# 16_LMS2_RF2_Misc.net
KiCad netlist of a schematic drawn in Altium Designer
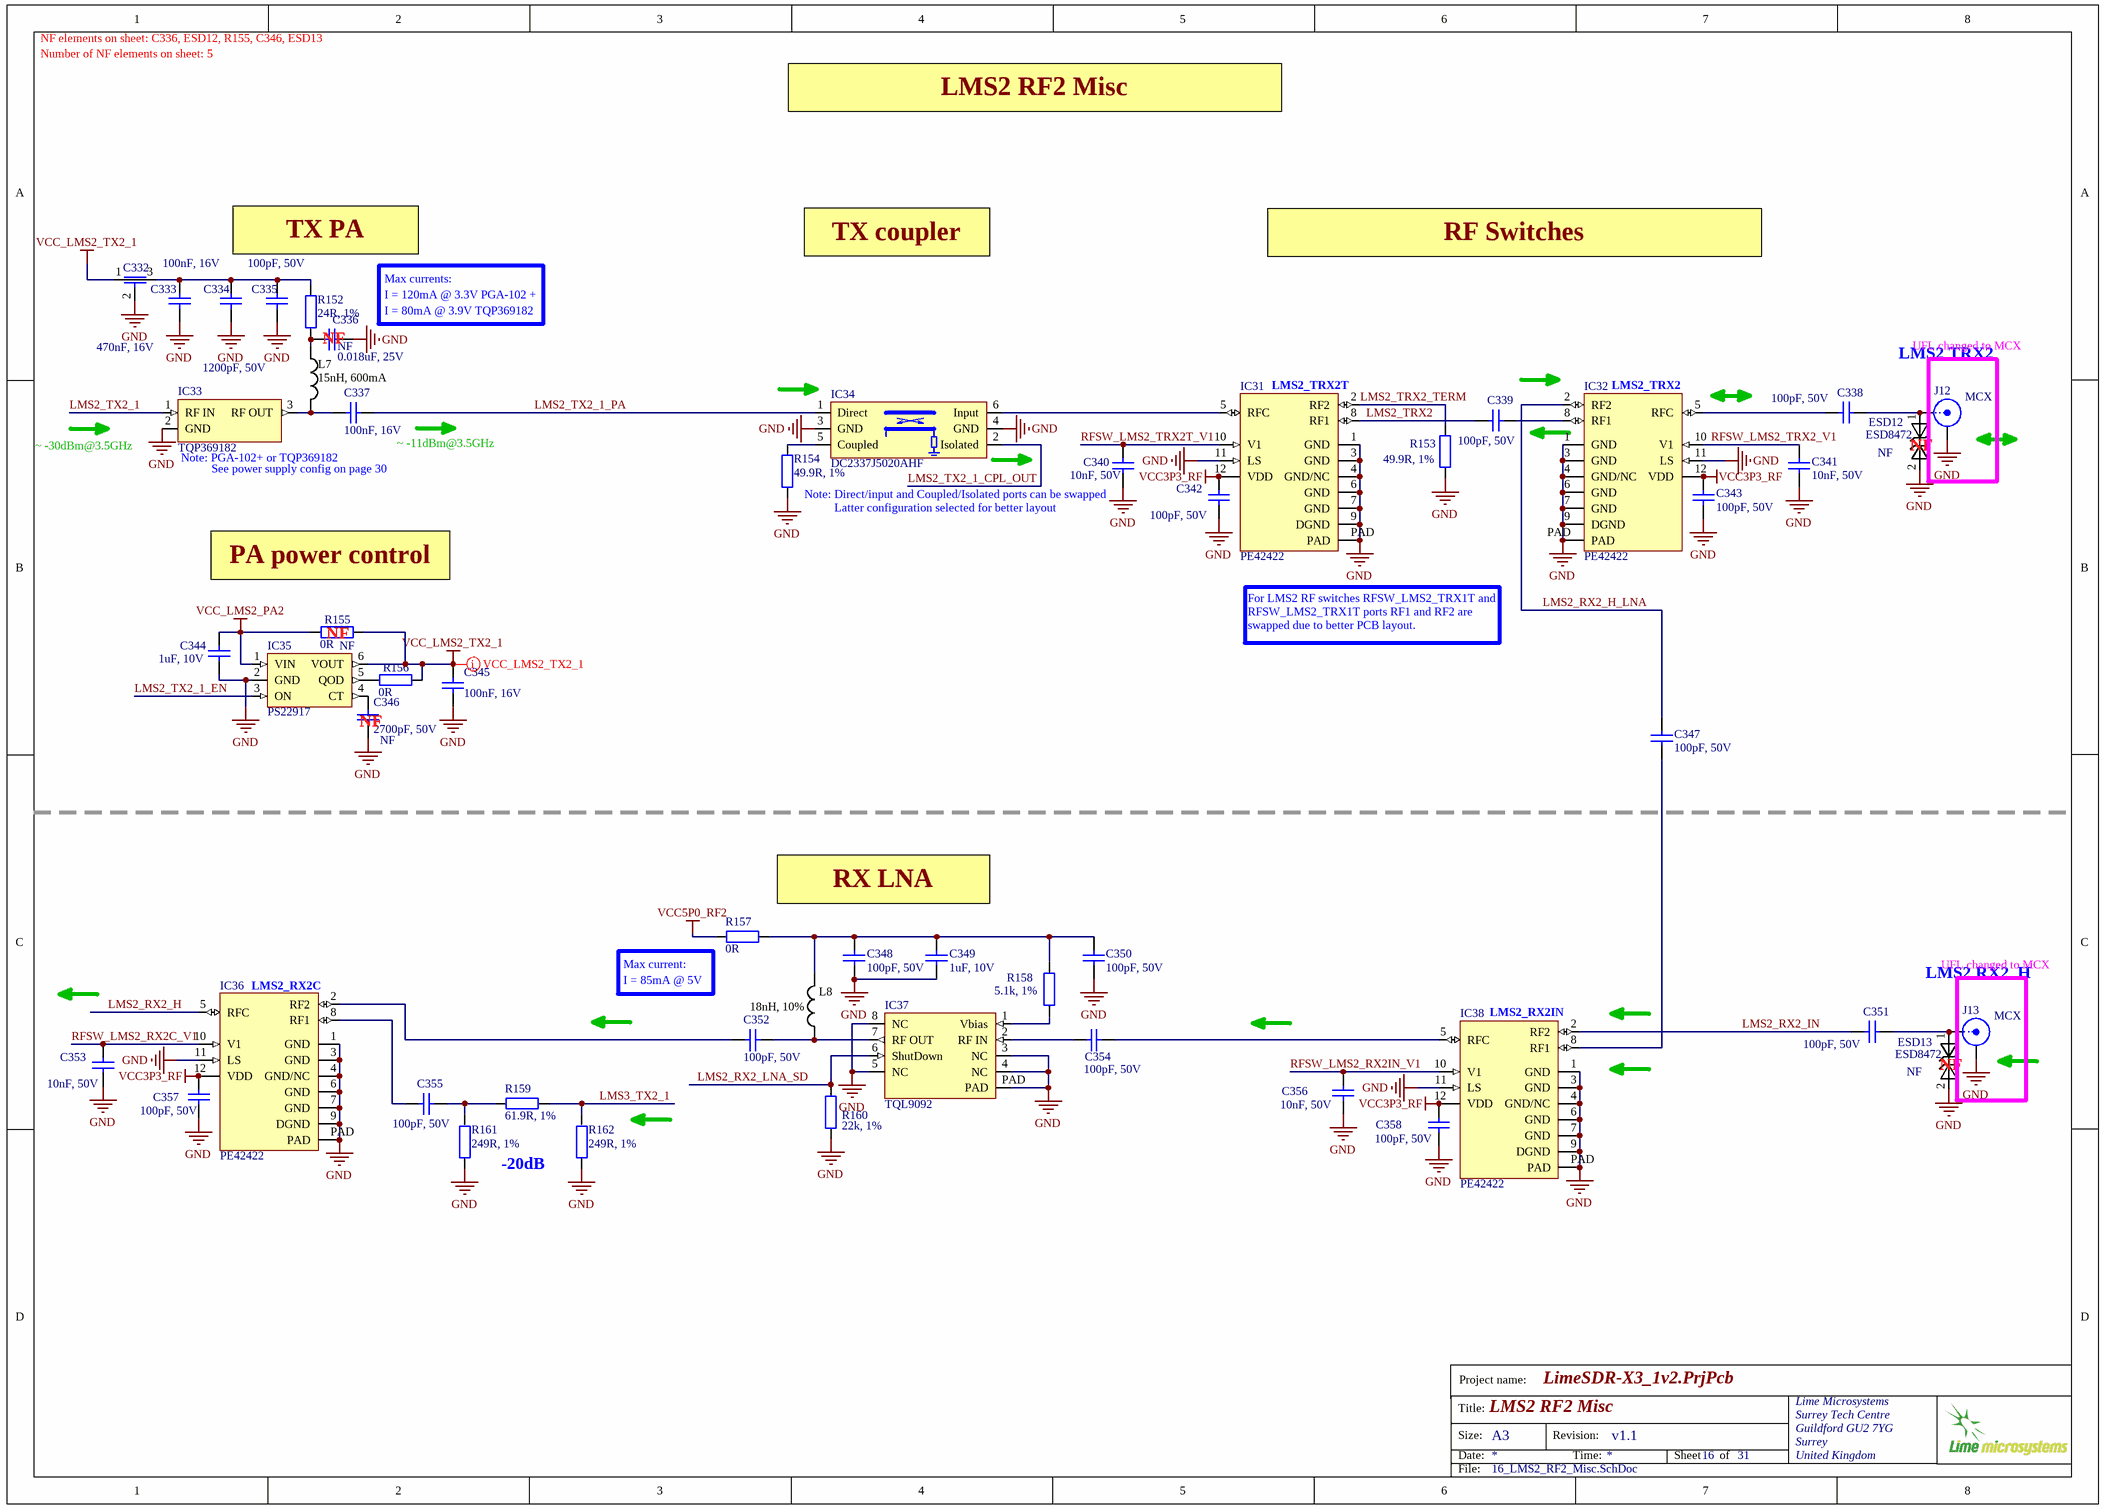
[diagram p0: 16_LMS2_RF2_Misc.SchDoc]

(export (version "E")
  (design (tool "Eeschema 10.0.6"))
  (components
    (comp (ref "C332")
      (value "470nF, 16V")
      (footprint "CAP0805_FEEDTHROUGH")
      (fields
        (field (name "MANUFACTURER") "Murata")
        (field (name "TOLERANCE") "20%")
        (field (name "VOLTAGE") "16V")
      )
      (libsource (lib "LimeMicroAltiumLib_schLib_r01") (part "Cap_feed_through"))
    )
    (comp (ref "C333")
      (value "100nF, 16V")
      (footprint "CAP0402")
      (fields (field (name "MANUFACTURER") "Murata Electronics") (field (name "TOLERANCE") "10 %"))
      (libsource (lib "") (part "Cap_0402_9"))
    )
    (comp (ref "C334")
      (value "1200pF, 50V")
      (footprint "CAP0402")
      (fields (field (name "MANUFACTURER") "Kemet") (field (name "TOLERANCE") "±5%"))
      (libsource (lib "LimeMicroAltiumLib_schLib") (part "Cap_0402"))
    )
    (comp (ref "C335")
      (value "100pF, 50V")
      (footprint "CAP0402")
      (fields (field (name "TOLERANCE") "±5%") (field (name "MANUFACTURER") "Yageo"))
      (libsource (lib "") (part "Cap_0402_9"))
    )
    (comp (ref "C336")
      (value "0.018uF, 25V")
      (footprint "CAP0402")
      (fields
        (field (name "ASSEMBLY INFO") "NF")
        (field (name "MANUFACTURER") "Yageo")
        (field (name "TOLERANCE") "10%")
      )
      (libsource (lib "LimeMicroAltiumLib_schLib") (part "Cap_0402"))
    )
    (comp (ref "C337")
      (value "100nF, 16V")
      (footprint "CAP0402")
      (fields (field (name "MANUFACTURER") "Murata Electronics") (field (name "TOLERANCE") "10 %"))
      (libsource (lib "LimeMicroAltiumLib_schLib") (part "Cap_0402"))
    )
    (comp (ref "C338")
      (value "100pF, 50V")
      (footprint "CAP0402")
      (fields (field (name "TOLERANCE") "±5%") (field (name "MANUFACTURER") "Yageo"))
      (libsource (lib "") (part "Cap_0402_1"))
    )
    (comp (ref "C339")
      (value "100pF, 50V")
      (footprint "CAP0402")
      (fields (field (name "TOLERANCE") "±5%") (field (name "MANUFACTURER") "Yageo"))
      (libsource (lib "") (part "Cap_0402_1"))
    )
    (comp (ref "C340")
      (value "10nF, 50V")
      (footprint "CAP0402")
      (fields
        (field (name "MANUFACTURER") "Murata Electronics North America")
        (field (name "TOLERANCE") "±10%")
      )
      (libsource (lib "") (part "Cap_0402_2"))
    )
    (comp (ref "C341")
      (value "10nF, 50V")
      (footprint "CAP0402")
      (fields
        (field (name "MANUFACTURER") "Murata Electronics North America")
        (field (name "TOLERANCE") "±10%")
      )
      (libsource (lib "") (part "Cap_0402_2"))
    )
    (comp (ref "C342")
      (value "100pF, 50V")
      (footprint "CAP0402")
      (fields (field (name "TOLERANCE") "±5%") (field (name "MANUFACTURER") "Yageo"))
      (libsource (lib "") (part "Cap_0402_6"))
    )
    (comp (ref "C343")
      (value "100pF, 50V")
      (footprint "CAP0402")
      (fields (field (name "TOLERANCE") "±5%") (field (name "MANUFACTURER") "Yageo"))
      (libsource (lib "") (part "Cap_0402_6"))
    )
    (comp (ref "C344")
      (value "1uF, 10V")
      (footprint "CAP0402")
      (fields (field (name "MANUFACTURER") "TDK"))
      (libsource (lib "") (part "Cap_0402_5"))
    )
    (comp (ref "C345")
      (value "100nF, 16V")
      (footprint "CAP0402")
      (fields (field (name "MANUFACTURER") "Murata Electronics") (field (name "TOLERANCE") "10 %"))
      (libsource (lib "") (part "Cap_0402_5"))
    )
    (comp (ref "C346")
      (value "2700pF, 50V")
      (footprint "CAP0402")
      (fields
        (field (name "ASSEMBLY INFO") "NF")
        (field (name "TOLERANCE") "±10%")
        (field (name "MANUFACTURER") "Murata Electronics North America")
      )
      (libsource (lib "") (part "Cap_0402_9"))
    )
    (comp (ref "C347")
      (value "100pF, 50V")
      (footprint "CAP0402")
      (fields (field (name "TOLERANCE") "±5%") (field (name "MANUFACTURER") "Yageo"))
      (libsource (lib "") (part "Cap_0402_1"))
    )
    (comp (ref "C348")
      (value "100pF, 50V")
      (footprint "CAP0402")
      (fields (field (name "TOLERANCE") "±5%") (field (name "MANUFACTURER") "Yageo"))
      (libsource (lib "") (part "Cap_0402_3"))
    )
    (comp (ref "C349")
      (value "1uF, 10V")
      (footprint "CAP0402")
      (fields (field (name "MANUFACTURER") "TDK"))
      (libsource (lib "") (part "Cap_0402_8"))
    )
    (comp (ref "C350")
      (value "100pF, 50V")
      (footprint "CAP0402")
      (fields (field (name "TOLERANCE") "±5%") (field (name "MANUFACTURER") "Yageo"))
      (libsource (lib "") (part "Cap_0402_3"))
    )
    (comp (ref "C351")
      (value "100pF, 50V")
      (footprint "CAP0402")
      (fields (field (name "TOLERANCE") "±5%") (field (name "MANUFACTURER") "Yageo"))
      (libsource (lib "") (part "Cap_0402_1"))
    )
    (comp (ref "C352")
      (value "100pF, 50V")
      (footprint "CAP0402")
      (fields (field (name "TOLERANCE") "±5%") (field (name "MANUFACTURER") "Yageo"))
      (libsource (lib "") (part "Cap_0402_5"))
    )
    (comp (ref "C353")
      (value "10nF, 50V")
      (footprint "CAP0402")
      (fields
        (field (name "MANUFACTURER") "Murata Electronics North America")
        (field (name "TOLERANCE") "±10%")
      )
      (libsource (lib "") (part "Cap_0402_4"))
    )
    (comp (ref "C354")
      (value "100pF, 50V")
      (footprint "CAP0402")
      (fields (field (name "TOLERANCE") "±5%") (field (name "MANUFACTURER") "Yageo"))
      (libsource (lib "") (part "Cap_0402_10"))
    )
    (comp (ref "C355")
      (value "100pF, 50V")
      (footprint "CAP0402")
      (fields (field (name "TOLERANCE") "±5%") (field (name "MANUFACTURER") "Yageo"))
      (libsource (lib "") (part "Cap_0402_1"))
    )
    (comp (ref "C356")
      (value "10nF, 50V")
      (footprint "CAP0402")
      (fields
        (field (name "MANUFACTURER") "Murata Electronics North America")
        (field (name "TOLERANCE") "±10%")
      )
      (libsource (lib "LimeMicroAltiumLib_schLib") (part "Cap_0402"))
    )
    (comp (ref "C357")
      (value "100pF, 50V")
      (footprint "CAP0402")
      (fields (field (name "TOLERANCE") "±5%") (field (name "MANUFACTURER") "Yageo"))
      (libsource (lib "") (part "Cap_0402_7"))
    )
    (comp (ref "C358")
      (value "100pF, 50V")
      (footprint "CAP0402")
      (fields (field (name "TOLERANCE") "±5%") (field (name "MANUFACTURER") "Yageo"))
      (libsource (lib "LimeMicroAltiumLib_schLib") (part "Cap_0402"))
    )
    (comp (ref "ESD12")
      (value "ESD8472")
      (footprint "ESD8472_X3DFN2")
      (fields (field (name "MANUFACTURER") "ON Semiconductor") (field (name "ASSEMBLY INFO") "NF"))
      (libsource (lib "") (part "ESD8472_1"))
    )
    (comp (ref "ESD13")
      (value "ESD8472")
      (footprint "ESD8472_X3DFN2")
      (fields (field (name "MANUFACTURER") "ON Semiconductor") (field (name "ASSEMBLY INFO") "NF"))
      (libsource (lib "LimeMicroAltiumLib_schLib") (part "ESD8472"))
    )
    (comp (ref "IC31")
      (value "PE42422")
      (footprint "PE42422_QFN12")
      (fields (field (name "MANUFACTURER") "Peregrine Semiconductor"))
      (libsource (lib "") (part "PE42422_3"))
    )
    (comp (ref "IC32")
      (value "PE42422")
      (footprint "PE42422_QFN12")
      (fields (field (name "MANUFACTURER") "Peregrine Semiconductor"))
      (libsource (lib "") (part "PE42422_2"))
    )
    (comp (ref "IC33")
      (value "TQP369182")
      (footprint "PGA-102+_SOT89")
      (fields (field (name "MANUFACTURER") "Qorvo"))
      (libsource (lib "LimeMicroAltiumLib_schLib_r01") (part "PGA-102+_PA"))
    )
    (comp (ref "IC34")
      (value "DC2337J5020AHF")
      (footprint "DC2337J5020AHF_ANAREN_COUPLER_0805")
      (fields (field (name "MANUFACTURER") "Anaren"))
      (libsource (lib "LimeMicroAltiumLib_schLib_r02") (part "DC2337J5020AHF_coupler"))
    )
    (comp (ref "IC35")
      (value "PS22917")
      (footprint "SOT23-6")
      (fields (field (name "MANUFACTURER") "Texas Instruments"))
      (libsource (lib "LimeMicroAltiumLib_schLib") (part "TPS22918"))
    )
    (comp (ref "IC36")
      (value "PE42422")
      (footprint "PE42422_QFN12")
      (fields (field (name "MANUFACTURER") "Peregrine Semiconductor"))
      (libsource (lib "LimeMicroAltiumLib_schLib") (part "PE42422"))
    )
    (comp (ref "IC37")
      (value "TQL9092")
      (footprint "TQL9092")
      (fields (field (name "MANUFACTURER") "Qorvo"))
      (libsource (lib "LimeMicroAltiumLib_schLib") (part "TQL9092"))
    )
    (comp (ref "IC38")
      (value "PE42422")
      (footprint "PE42422_QFN12")
      (fields (field (name "MANUFACTURER") "Peregrine Semiconductor"))
      (libsource (lib "") (part "PE42422_1"))
    )
    (comp (ref "J12")
      (value "MCX")
      (footprint "MCX_connector_vertical_SM")
      (description "Conn MCX RCP 0Hz to 6GHz 50Ohm Solder ST SMD Gold Over Nickel Stock")
      (fields (field (name "MANUFACTURER") "Bel Cinch"))
      (libsource (lib "LimeMicroAltiumLib_schLib") (part "RF_IF_connector"))
    )
    (comp (ref "J13")
      (value "MCX")
      (footprint "MCX_connector_vertical_SM")
      (description "Conn MCX RCP 0Hz to 6GHz 50Ohm Solder ST SMD Gold Over Nickel Stock")
      (fields (field (name "MANUFACTURER") "Bel Cinch"))
      (libsource (lib "LimeMicroAltiumLib_schLib") (part "RF_IF_connector"))
    )
    (comp (ref "L7")
      (value "15nH, 600mA")
      (footprint "RES0805")
      (fields (field (name "MANUFACTURER") "Bourns") (field (name "TOLERANCE") "5%"))
      (libsource (lib "LimeMicroAltiumLib_schLib") (part "Inductor_0603"))
    )
    (comp (ref "L8")
      (value "18nH, 10%")
      (footprint "RES0603")
      (fields (field (name "MANUFACTURER") "Pulse Electronics Network") (field (name "TOLERANCE") "±10%"))
      (libsource (lib "LimeMicroAltiumLib_schLib") (part "Inductor"))
    )
    (comp (ref "R152")
      (value "24R, 1%")
      (footprint "RES0402")
      (fields (field (name "MANUFACTURER") "Yageo") (field (name "TOLERANCE") "1%"))
      (libsource (lib "LimeFPGAboard_schLib") (part "Res_0402"))
    )
    (comp (ref "R153")
      (value "49.9R, 1%")
      (footprint "RES0402")
      (fields
        (field (name "TOLERANCE") "±1%")
        (field (name "MANUFACTURER") "Samsung Electro-Mechanics America, Inc.")
        (field (name "MANUFACTURER PART NUMBER") "RC1005F49R9CS")
      )
      (libsource (lib "") (part "Res_0402_1"))
    )
    (comp (ref "R154")
      (value "49.9R, 1%")
      (footprint "RES0402")
      (fields
        (field (name "TOLERANCE") "±1%")
        (field (name "MANUFACTURER") "Samsung Electro-Mechanics America, Inc.")
        (field (name "MANUFACTURER PART NUMBER") "RC1005F49R9CS")
      )
      (libsource (lib "") (part "Res_0402_1"))
    )
    (comp (ref "R155")
      (value "0R")
      (footprint "RES0402")
      (fields
        (field (name "ASSEMBLY INFO") "NF")
        (field (name "MANUFACTURER") "Yageo")
        (field (name "TOLERANCE") "Jumper")
      )
      (libsource (lib "LimeMicroAltiumLib_schLib") (part "Res_0402"))
    )
    (comp (ref "R156")
      (value "0R")
      (footprint "RES0402")
      (fields (field (name "MANUFACTURER") "Yageo") (field (name "TOLERANCE") "Jumper"))
      (libsource (lib "LimeMicroAltiumLib_schLib") (part "Res_0402"))
    )
    (comp (ref "R157")
      (value "0R")
      (footprint "RES0402")
      (fields (field (name "MANUFACTURER") "Yageo") (field (name "TOLERANCE") "Jumper"))
      (libsource (lib "") (part "Res_0402_1"))
    )
    (comp (ref "R158")
      (value "5.1k, 1%")
      (footprint "RES0603")
      (fields (field (name "MANUFACTURER") "Stackpole Electronics") (field (name "TOLERANCE") "1%"))
      (libsource (lib "LimeMicroAltiumLib_schLib") (part "Res_0603"))
    )
    (comp (ref "R159")
      (value "61.9R, 1%")
      (footprint "RES0402")
      (fields (field (name "MANUFACTURER") "Yageo") (field (name "TOLERANCE") "1%"))
      (libsource (lib "LimeMicroAltiumLib_schLib") (part "Res_0402"))
    )
    (comp (ref "R160")
      (value "22k, 1%")
      (footprint "RES0402")
      (fields (field (name "MANUFACTURER") "Yageo") (field (name "TOLERANCE") "±1%"))
      (libsource (lib "LimeMicroAltiumLib_schLib") (part "Res_0402"))
    )
    (comp (ref "R161")
      (value "249R, 1%")
      (footprint "RES0402")
      (fields (field (name "MANUFACTURER") "Stackpole Electronics Inc") (field (name "TOLERANCE") "±1%"))
      (libsource (lib "LimeMicroAltiumLib_schLib") (part "Res_0402"))
    )
    (comp (ref "R162")
      (value "249R, 1%")
      (footprint "RES0402")
      (fields (field (name "MANUFACTURER") "Stackpole Electronics Inc") (field (name "TOLERANCE") "±1%"))
      (libsource (lib "LimeMicroAltiumLib_schLib") (part "Res_0402"))
    )
  )
  (nets
    (net (code "1") (name "/LMS2_RX2_H") (class "Default")
      (node (ref "IC36") (pin "5") (pinfunction "RFC_5") (pintype "bidirectional"))
    )
    (net (code "2") (name "/LMS2_RX2_H_LNA") (class "Default")
      (node (ref "C347") (pin "2") (pinfunction "2_2") (pintype "passive"))
      (node (ref "IC32") (pin "2") (pinfunction "RF2_2") (pintype "bidirectional"))
    )
    (net (code "3") (name "/LMS2_RX2_IN") (class "Default")
      (node (ref "C351") (pin "1") (pinfunction "1_1") (pintype "passive"))
      (node (ref "IC38") (pin "2") (pinfunction "RF2_2") (pintype "bidirectional"))
    )
    (net (code "4") (name "/LMS2_RX2_LNA_SD") (class "Default")
      (node (ref "IC37") (pin "6") (pinfunction "ShutDown_6") (pintype "input"))
      (node (ref "R160") (pin "2") (pinfunction "2_2") (pintype "passive"))
    )
    (net (code "5") (name "/LMS2_TRX2") (class "Default")
      (node (ref "C339") (pin "1") (pinfunction "1_1") (pintype "passive"))
      (node (ref "IC31") (pin "8") (pinfunction "RF1_8") (pintype "bidirectional"))
    )
    (net (code "6") (name "/LMS2_TRX2_TERM") (class "Default")
      (node (ref "IC31") (pin "2") (pinfunction "RF2_2") (pintype "bidirectional"))
      (node (ref "R153") (pin "1") (pinfunction "1_1") (pintype "passive"))
    )
    (net (code "7") (name "/LMS2_TX2_1") (class "Default")
      (node (ref "IC33") (pin "1") (pinfunction "RF_IN_1") (pintype "input"))
    )
    (net (code "8") (name "/LMS2_TX2_1_CPL_OUT") (class "Default")
      (node (ref "IC34") (pin "2") (pinfunction "Isolated_2") (pintype "passive"))
    )
    (net (code "9") (name "/LMS2_TX2_1_EN") (class "Default")
      (node (ref "IC35") (pin "3") (pinfunction "ON_3") (pintype "input"))
    )
    (net (code "10") (name "/LMS2_TX2_1_PA") (class "Default")
      (node (ref "C337") (pin "1") (pinfunction "1_1") (pintype "passive"))
      (node (ref "IC34") (pin "1") (pinfunction "Direct_1") (pintype "passive"))
    )
    (net (code "11") (name "/LMS3_TX2_1") (class "Default")
      (node (ref "R159") (pin "2") (pinfunction "2_2") (pintype "passive"))
      (node (ref "R162") (pin "2") (pinfunction "2_2") (pintype "passive"))
    )
    (net (code "12") (name "/RFSW_LMS2_RX2C_V1") (class "Default")
      (node (ref "C353") (pin "1") (pinfunction "1_1") (pintype "passive"))
      (node (ref "IC36") (pin "10") (pinfunction "V1_10") (pintype "input"))
    )
    (net (code "13") (name "/RFSW_LMS2_RX2IN_V1") (class "Default")
      (node (ref "C356") (pin "1") (pinfunction "1_1") (pintype "passive"))
      (node (ref "IC38") (pin "10") (pinfunction "V1_10") (pintype "input"))
    )
    (net (code "14") (name "/RFSW_LMS2_TRX2T_V1") (class "Default")
      (node (ref "C340") (pin "1") (pinfunction "1_1") (pintype "passive"))
      (node (ref "IC31") (pin "10") (pinfunction "V1_10") (pintype "input"))
    )
    (net (code "15") (name "/RFSW_LMS2_TRX2_V1") (class "Default")
      (node (ref "C341") (pin "1") (pinfunction "1_1") (pintype "passive"))
      (node (ref "IC32") (pin "10") (pinfunction "V1_10") (pintype "input"))
    )
    (net (code "16") (name "GND") (class "Default")
      (node (ref "C332") (pin "2") (pinfunction "2_2") (pintype "passive"))
      (node (ref "C333") (pin "1") (pinfunction "1_1") (pintype "passive"))
      (node (ref "C334") (pin "2") (pinfunction "2_2") (pintype "passive"))
      (node (ref "C335") (pin "2") (pinfunction "2_2") (pintype "passive"))
      (node (ref "C336") (pin "2") (pinfunction "2_2") (pintype "passive"))
      (node (ref "C340") (pin "2") (pinfunction "2_2") (pintype "passive"))
      (node (ref "C341") (pin "2") (pinfunction "2_2") (pintype "passive"))
      (node (ref "C342") (pin "1") (pinfunction "1_1") (pintype "passive"))
      (node (ref "C343") (pin "1") (pinfunction "1_1") (pintype "passive"))
      (node (ref "C344") (pin "1") (pinfunction "1_1") (pintype "passive"))
      (node (ref "C345") (pin "1") (pinfunction "1_1") (pintype "passive"))
      (node (ref "C346") (pin "2") (pinfunction "2_2") (pintype "passive"))
      (node (ref "C348") (pin "2") (pinfunction "2_2") (pintype "passive"))
      (node (ref "C349") (pin "1") (pinfunction "1_1") (pintype "passive"))
      (node (ref "C350") (pin "2") (pinfunction "2_2") (pintype "passive"))
      (node (ref "C353") (pin "2") (pinfunction "2_2") (pintype "passive"))
      (node (ref "C356") (pin "2") (pinfunction "2_2") (pintype "passive"))
      (node (ref "C357") (pin "1") (pinfunction "1_1") (pintype "passive"))
      (node (ref "C358") (pin "1") (pinfunction "1_1") (pintype "passive"))
      (node (ref "ESD12") (pin "2") (pinfunction "2_2") (pintype "passive"))
      (node (ref "ESD13") (pin "2") (pinfunction "2_2") (pintype "passive"))
      (node (ref "IC31") (pin "1") (pinfunction "GND_1") (pintype "passive"))
      (node (ref "IC31") (pin "11") (pinfunction "LS_11") (pintype "input"))
      (node (ref "IC31") (pin "3") (pinfunction "GND_3") (pintype "passive"))
      (node (ref "IC31") (pin "4") (pinfunction "GND/NC_4") (pintype "passive"))
      (node (ref "IC31") (pin "6") (pinfunction "GND_6") (pintype "passive"))
      (node (ref "IC31") (pin "7") (pinfunction "GND_7") (pintype "passive"))
      (node (ref "IC31") (pin "9") (pinfunction "DGND_9") (pintype "passive"))
      (node (ref "IC31") (pin "PAD") (pinfunction "PAD_PAD") (pintype "passive"))
      (node (ref "IC32") (pin "1") (pinfunction "GND_1") (pintype "passive"))
      (node (ref "IC32") (pin "11") (pinfunction "LS_11") (pintype "input"))
      (node (ref "IC32") (pin "3") (pinfunction "GND_3") (pintype "passive"))
      (node (ref "IC32") (pin "4") (pinfunction "GND/NC_4") (pintype "passive"))
      (node (ref "IC32") (pin "6") (pinfunction "GND_6") (pintype "passive"))
      (node (ref "IC32") (pin "7") (pinfunction "GND_7") (pintype "passive"))
      (node (ref "IC32") (pin "9") (pinfunction "DGND_9") (pintype "passive"))
      (node (ref "IC32") (pin "PAD") (pinfunction "PAD_PAD") (pintype "passive"))
      (node (ref "IC33") (pin "2") (pinfunction "GND_2") (pintype "passive"))
      (node (ref "IC34") (pin "3") (pinfunction "GND_3") (pintype "passive"))
      (node (ref "IC34") (pin "4") (pinfunction "GND_4") (pintype "passive"))
      (node (ref "IC35") (pin "2") (pinfunction "GND_2") (pintype "passive"))
      (node (ref "IC36") (pin "1") (pinfunction "GND_1") (pintype "passive"))
      (node (ref "IC36") (pin "11") (pinfunction "LS_11") (pintype "input"))
      (node (ref "IC36") (pin "3") (pinfunction "GND_3") (pintype "passive"))
      (node (ref "IC36") (pin "4") (pinfunction "GND/NC_4") (pintype "passive"))
      (node (ref "IC36") (pin "6") (pinfunction "GND_6") (pintype "passive"))
      (node (ref "IC36") (pin "7") (pinfunction "GND_7") (pintype "passive"))
      (node (ref "IC36") (pin "9") (pinfunction "DGND_9") (pintype "passive"))
      (node (ref "IC36") (pin "PAD") (pinfunction "PAD_PAD") (pintype "passive"))
      (node (ref "IC37") (pin "3") (pinfunction "NC_3") (pintype "passive"))
      (node (ref "IC37") (pin "4") (pinfunction "NC_4") (pintype "passive"))
      (node (ref "IC37") (pin "5") (pinfunction "NC_5") (pintype "passive"))
      (node (ref "IC37") (pin "8") (pinfunction "NC_8") (pintype "passive"))
      (node (ref "IC37") (pin "PAD") (pinfunction "PAD_PAD") (pintype "passive"))
      (node (ref "IC38") (pin "1") (pinfunction "GND_1") (pintype "passive"))
      (node (ref "IC38") (pin "11") (pinfunction "LS_11") (pintype "input"))
      (node (ref "IC38") (pin "3") (pinfunction "GND_3") (pintype "passive"))
      (node (ref "IC38") (pin "4") (pinfunction "GND/NC_4") (pintype "passive"))
      (node (ref "IC38") (pin "6") (pinfunction "GND_6") (pintype "passive"))
      (node (ref "IC38") (pin "7") (pinfunction "GND_7") (pintype "passive"))
      (node (ref "IC38") (pin "9") (pinfunction "DGND_9") (pintype "passive"))
      (node (ref "IC38") (pin "PAD") (pinfunction "PAD_PAD") (pintype "passive"))
      (node (ref "J12") (pin "2") (pinfunction "Y_2") (pintype "passive"))
      (node (ref "J13") (pin "2") (pinfunction "Y_2") (pintype "passive"))
      (node (ref "R153") (pin "2") (pinfunction "2_2") (pintype "passive"))
      (node (ref "R154") (pin "2") (pinfunction "2_2") (pintype "passive"))
      (node (ref "R160") (pin "1") (pinfunction "1_1") (pintype "passive"))
      (node (ref "R161") (pin "1") (pinfunction "1_1") (pintype "passive"))
      (node (ref "R162") (pin "1") (pinfunction "1_1") (pintype "passive"))
    )
    (net (code "17") (name "Net-(C332-Pad3)") (class "Default")
      (node (ref "C332") (pin "3") (pinfunction "3_3") (pintype "passive"))
      (node (ref "C333") (pin "2") (pinfunction "2_2") (pintype "passive"))
      (node (ref "C334") (pin "1") (pinfunction "1_1") (pintype "passive"))
      (node (ref "C335") (pin "1") (pinfunction "1_1") (pintype "passive"))
      (node (ref "R152") (pin "1") (pinfunction "1_1") (pintype "passive"))
    )
    (net (code "18") (name "Net-(C336-Pad1)") (class "Default")
      (node (ref "C336") (pin "1") (pinfunction "1_1") (pintype "passive"))
      (node (ref "L7") (pin "1") (pinfunction "1_1") (pintype "passive"))
      (node (ref "R152") (pin "2") (pinfunction "2_2") (pintype "passive"))
    )
    (net (code "19") (name "Net-(C348-Pad1)") (class "Default")
      (node (ref "C348") (pin "1") (pinfunction "1_1") (pintype "passive"))
      (node (ref "C349") (pin "2") (pinfunction "2_2") (pintype "passive"))
      (node (ref "C350") (pin "1") (pinfunction "1_1") (pintype "passive"))
      (node (ref "L8") (pin "1") (pinfunction "1_1") (pintype "passive"))
      (node (ref "R157") (pin "2") (pinfunction "2_2") (pintype "passive"))
      (node (ref "R158") (pin "2") (pinfunction "2_2") (pintype "passive"))
    )
    (net (code "20") (name "Net-(C355-Pad1)") (class "Default")
      (node (ref "C355") (pin "1") (pinfunction "1_1") (pintype "passive"))
      (node (ref "R159") (pin "1") (pinfunction "1_1") (pintype "passive"))
      (node (ref "R161") (pin "2") (pinfunction "2_2") (pintype "passive"))
    )
    (net (code "21") (name "Net-(IC31-RFC)") (class "Default")
      (node (ref "IC31") (pin "5") (pinfunction "RFC_5") (pintype "bidirectional"))
      (node (ref "IC34") (pin "6") (pinfunction "Input_6") (pintype "passive"))
    )
    (net (code "22") (name "Net-(IC32-RF1)") (class "Default")
      (node (ref "C339") (pin "2") (pinfunction "2_2") (pintype "passive"))
      (node (ref "IC32") (pin "8") (pinfunction "RF1_8") (pintype "bidirectional"))
    )
    (net (code "23") (name "Net-(IC32-RFC)") (class "Default")
      (node (ref "C338") (pin "1") (pinfunction "1_1") (pintype "passive"))
      (node (ref "IC32") (pin "5") (pinfunction "RFC_5") (pintype "bidirectional"))
    )
    (net (code "24") (name "Net-(IC33-RF_OUT)") (class "Default")
      (node (ref "C337") (pin "2") (pinfunction "2_2") (pintype "passive"))
      (node (ref "IC33") (pin "3") (pinfunction "RF_OUT_3") (pintype "output"))
      (node (ref "L7") (pin "2") (pinfunction "2_2") (pintype "passive"))
    )
    (net (code "25") (name "Net-(IC34-Coupled)") (class "Default")
      (node (ref "IC34") (pin "5") (pinfunction "Coupled_5") (pintype "passive"))
      (node (ref "R154") (pin "1") (pinfunction "1_1") (pintype "passive"))
    )
    (net (code "26") (name "Net-(IC35-CT)") (class "Default")
      (node (ref "C346") (pin "1") (pinfunction "1_1") (pintype "passive"))
      (node (ref "IC35") (pin "4") (pinfunction "CT_4") (pintype "output"))
    )
    (net (code "27") (name "Net-(IC35-QOD)") (class "Default")
      (node (ref "IC35") (pin "5") (pinfunction "QOD_5") (pintype "output"))
      (node (ref "R156") (pin "2") (pinfunction "2_2") (pintype "passive"))
    )
    (net (code "28") (name "Net-(IC36-RF1)") (class "Default")
      (node (ref "C355") (pin "2") (pinfunction "2_2") (pintype "passive"))
      (node (ref "IC36") (pin "8") (pinfunction "RF1_8") (pintype "bidirectional"))
    )
    (net (code "29") (name "Net-(IC36-RF2)") (class "Default")
      (node (ref "C352") (pin "1") (pinfunction "1_1") (pintype "passive"))
      (node (ref "IC36") (pin "2") (pinfunction "RF2_2") (pintype "bidirectional"))
    )
    (net (code "30") (name "Net-(IC37-RF_IN)") (class "Default")
      (node (ref "C354") (pin "1") (pinfunction "1_1") (pintype "passive"))
      (node (ref "IC37") (pin "2") (pinfunction "RF_IN_2") (pintype "input"))
    )
    (net (code "31") (name "Net-(IC37-RF_OUT)") (class "Default")
      (node (ref "C352") (pin "2") (pinfunction "2_2") (pintype "passive"))
      (node (ref "IC37") (pin "7") (pinfunction "RF_OUT_7") (pintype "output"))
      (node (ref "L8") (pin "2") (pinfunction "2_2") (pintype "passive"))
    )
    (net (code "32") (name "Net-(IC37-Vbias)") (class "Default")
      (node (ref "IC37") (pin "1") (pinfunction "Vbias_1") (pintype "input"))
      (node (ref "R158") (pin "1") (pinfunction "1_1") (pintype "passive"))
    )
    (net (code "33") (name "Net-(IC38-RF1)") (class "Default")
      (node (ref "C347") (pin "1") (pinfunction "1_1") (pintype "passive"))
      (node (ref "IC38") (pin "8") (pinfunction "RF1_8") (pintype "bidirectional"))
    )
    (net (code "34") (name "Net-(IC38-RFC)") (class "Default")
      (node (ref "C354") (pin "2") (pinfunction "2_2") (pintype "passive"))
      (node (ref "IC38") (pin "5") (pinfunction "RFC_5") (pintype "bidirectional"))
    )
    (net (code "35") (name "Net-(J12-X)") (class "Default")
      (node (ref "C338") (pin "2") (pinfunction "2_2") (pintype "passive"))
      (node (ref "ESD12") (pin "1") (pinfunction "1_1") (pintype "passive"))
      (node (ref "J12") (pin "1") (pinfunction "X_1") (pintype "passive"))
    )
    (net (code "36") (name "Net-(J13-X)") (class "Default")
      (node (ref "C351") (pin "2") (pinfunction "2_2") (pintype "passive"))
      (node (ref "ESD13") (pin "1") (pinfunction "1_1") (pintype "passive"))
      (node (ref "J13") (pin "1") (pinfunction "X_1") (pintype "passive"))
    )
    (net (code "37") (name "VCC3P3_RF") (class "Default")
      (node (ref "C342") (pin "2") (pinfunction "2_2") (pintype "passive"))
      (node (ref "C343") (pin "2") (pinfunction "2_2") (pintype "passive"))
      (node (ref "C357") (pin "2") (pinfunction "2_2") (pintype "passive"))
      (node (ref "C358") (pin "2") (pinfunction "2_2") (pintype "passive"))
      (node (ref "IC31") (pin "12") (pinfunction "VDD_12") (pintype "power_in"))
      (node (ref "IC32") (pin "12") (pinfunction "VDD_12") (pintype "power_in"))
      (node (ref "IC36") (pin "12") (pinfunction "VDD_12") (pintype "power_in"))
      (node (ref "IC38") (pin "12") (pinfunction "VDD_12") (pintype "power_in"))
    )
    (net (code "38") (name "VCC5P0_RF2") (class "Default")
      (node (ref "R157") (pin "1") (pinfunction "1_1") (pintype "passive"))
    )
    (net (code "39") (name "VCC_LMS2_PA2") (class "Default")
      (node (ref "C344") (pin "2") (pinfunction "2_2") (pintype "passive"))
      (node (ref "IC35") (pin "1") (pinfunction "VIN_1") (pintype "input"))
      (node (ref "R155") (pin "2") (pinfunction "2_2") (pintype "passive"))
    )
    (net (code "40") (name "VCC_LMS2_TX2_1") (class "Default")
      (node (ref "C332") (pin "1") (pinfunction "1_1") (pintype "passive"))
      (node (ref "C345") (pin "2") (pinfunction "2_2") (pintype "passive"))
      (node (ref "IC35") (pin "6") (pinfunction "VOUT_6") (pintype "output"))
      (node (ref "R155") (pin "1") (pinfunction "1_1") (pintype "passive"))
      (node (ref "R156") (pin "1") (pinfunction "1_1") (pintype "passive"))
    )
  )
)
